# TG21_Slave_Device_Amply.net
KiCad netlist of a schematic drawn in Altium Designer
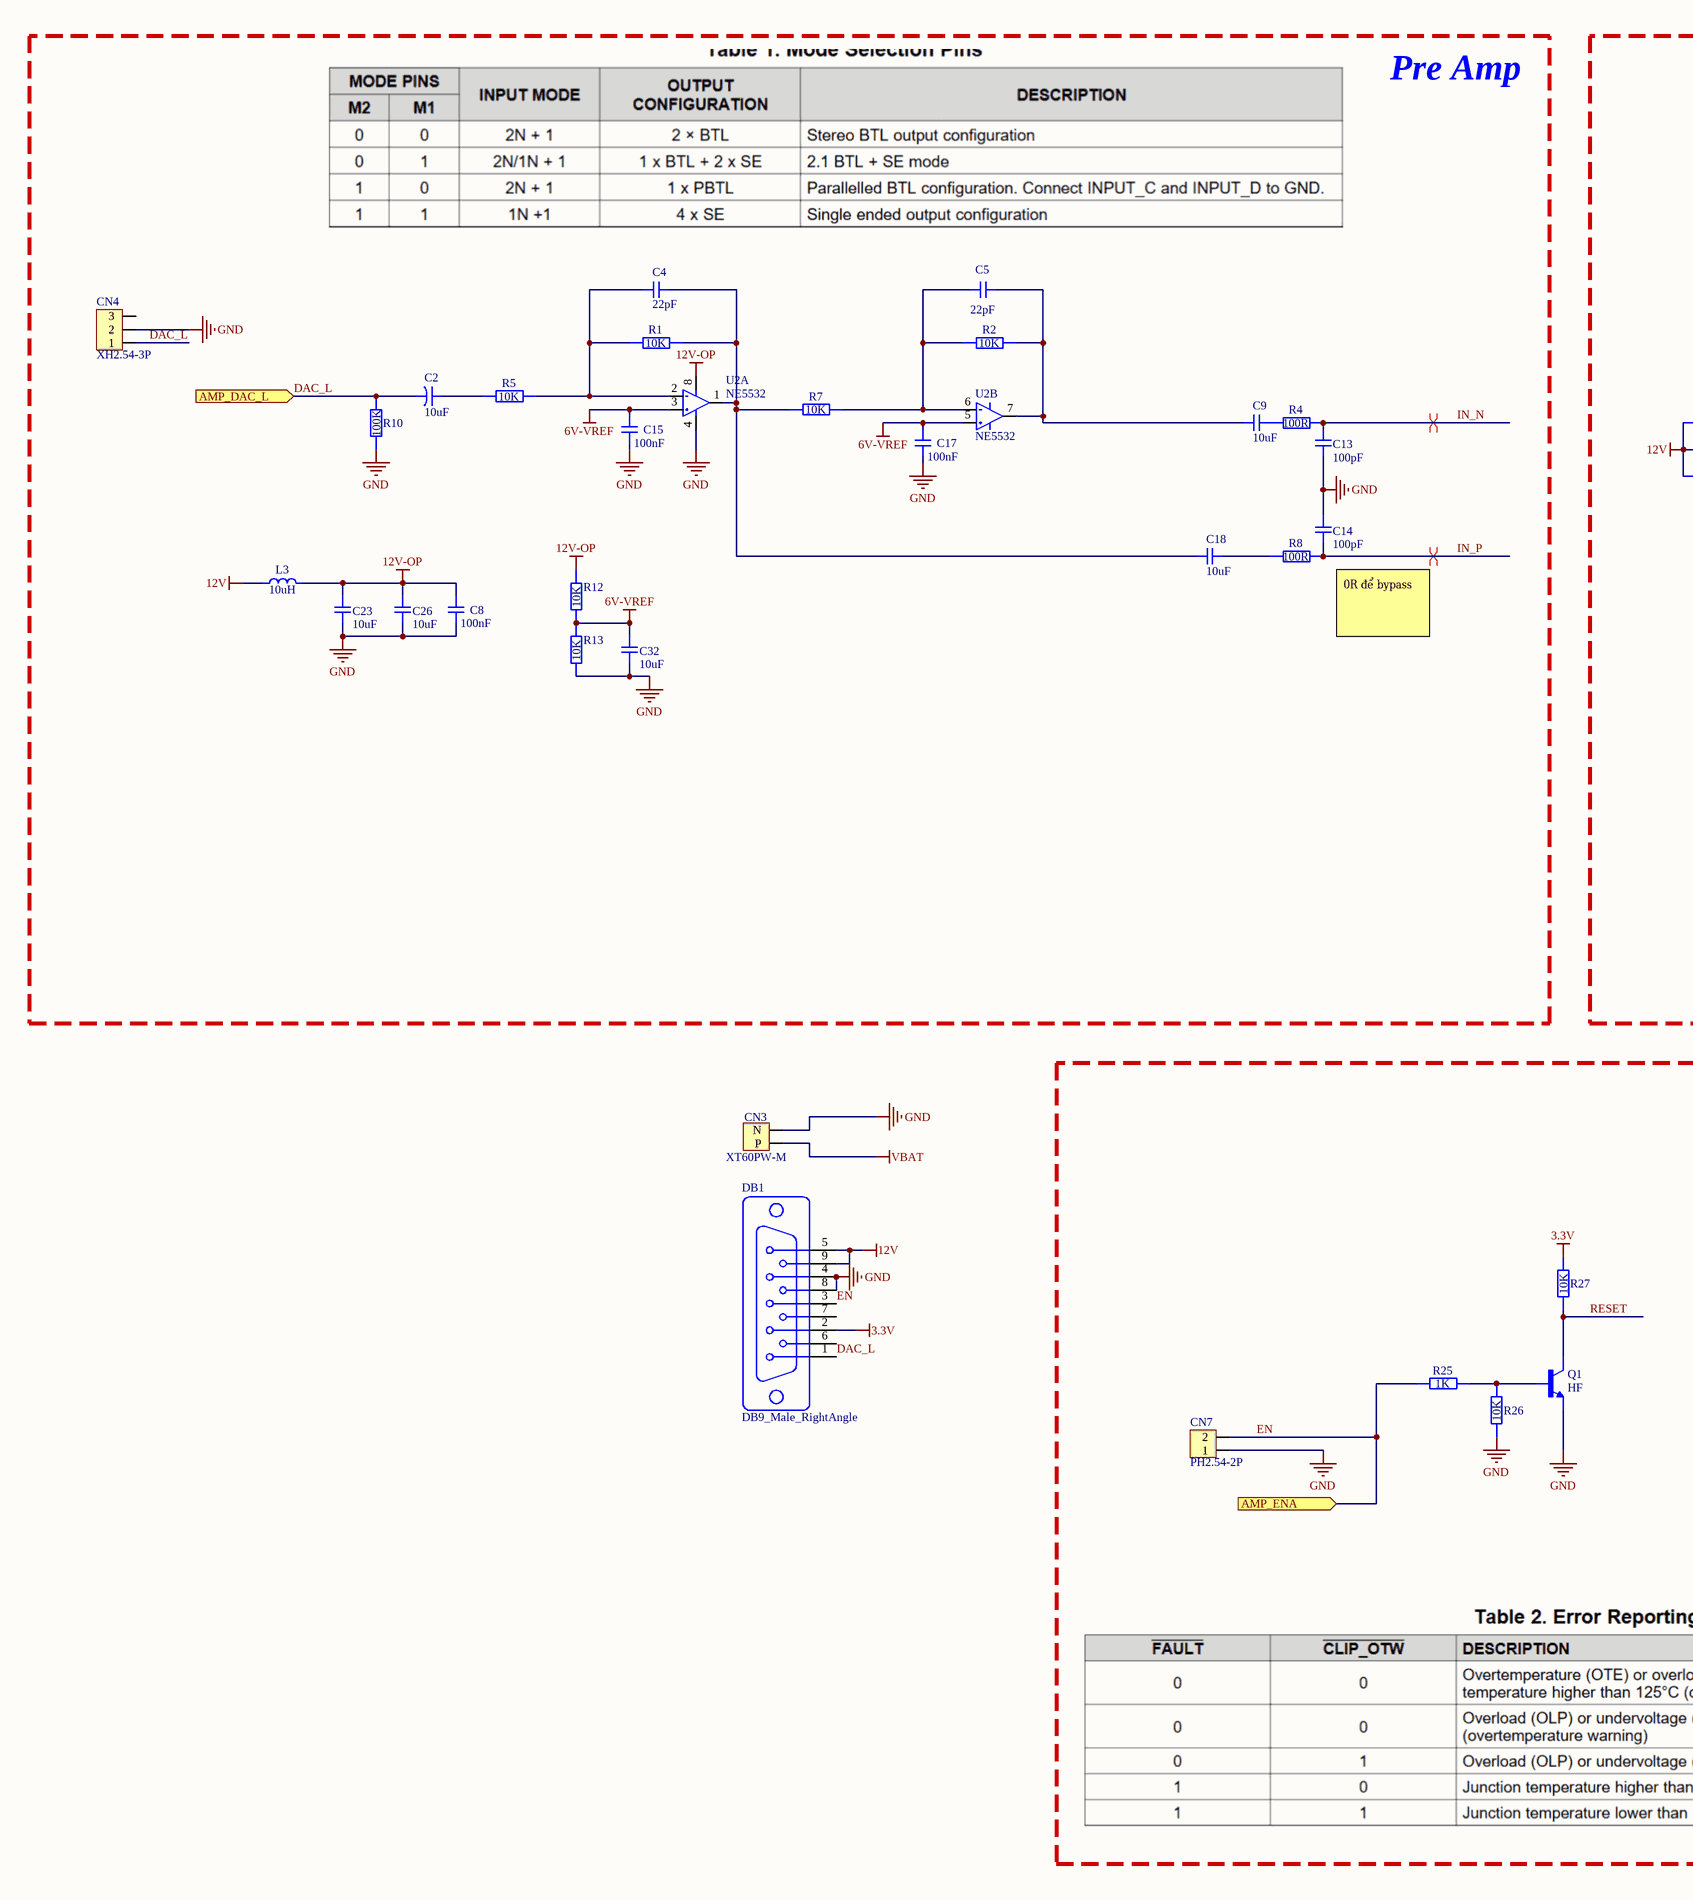
[diagram p0: TG21_Slave_Device_Amply.SchDoc, left]
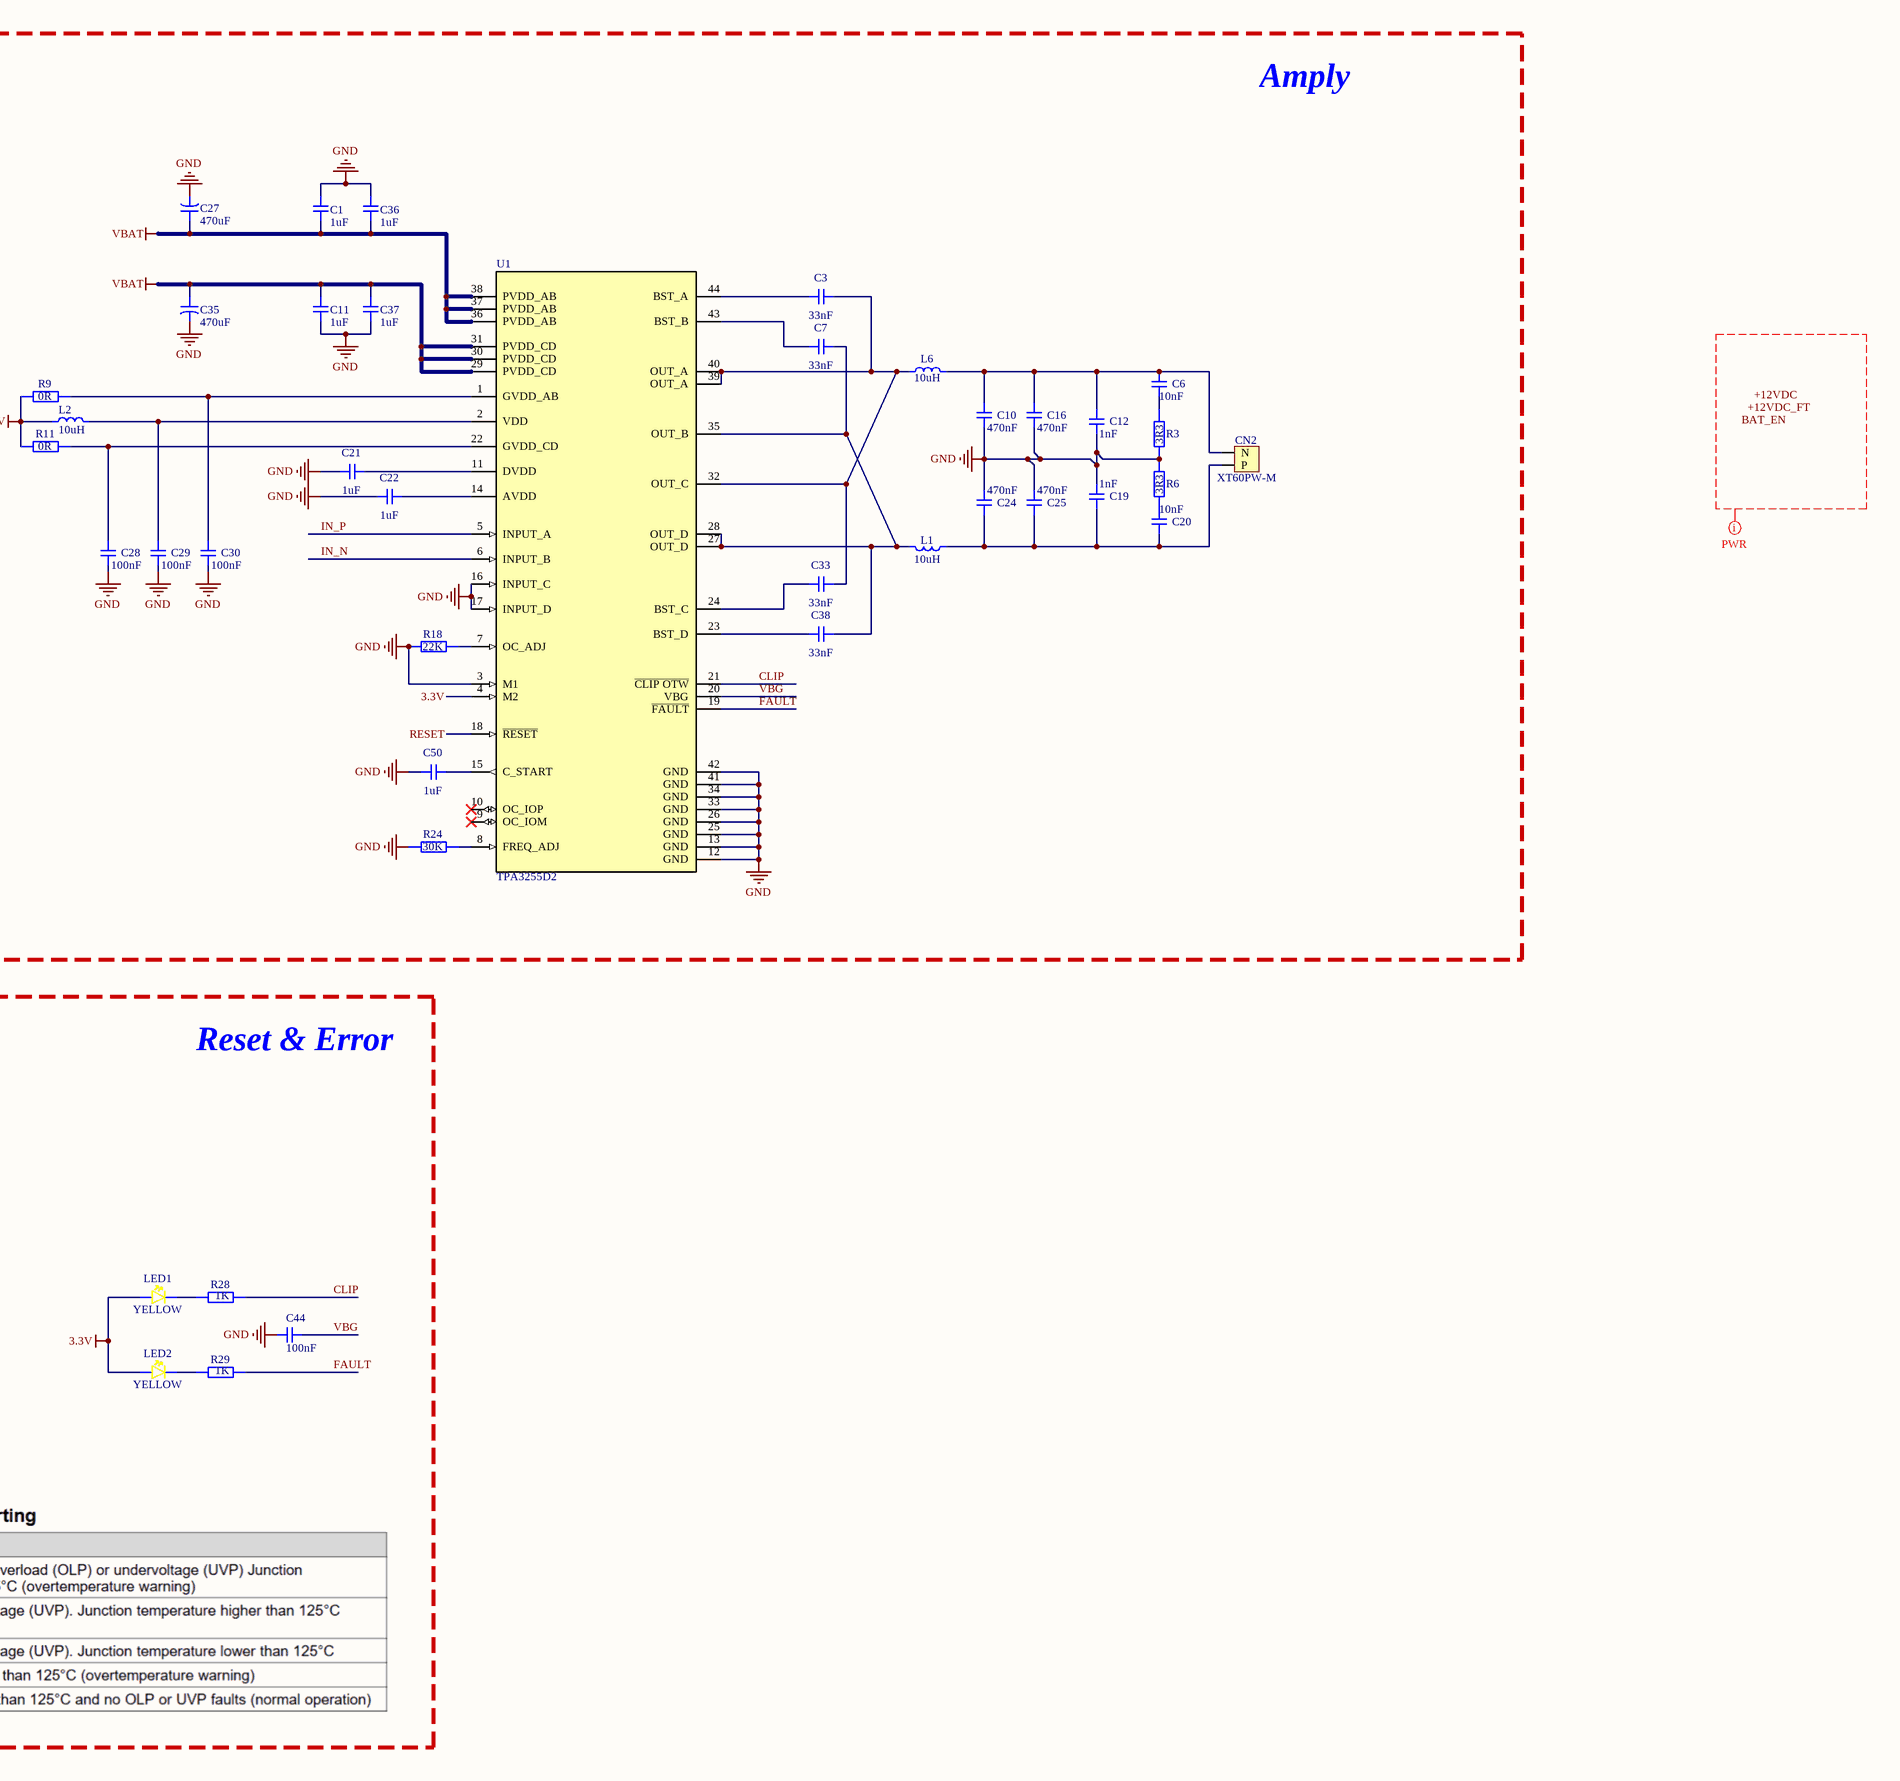
[diagram p1: TG21_Slave_Device_Amply.SchDoc, right]

(export (version "E")
  (design (tool "Eeschema 10.0.6"))
  (components
    (comp (ref "C1")
      (value "1uF")
      (footprint "CAP-0603")
      (description "1uF ±10% 50V Ceramic Capacitor X7R 0603")
      (fields (field (name "MANUFACTURER") "YAGEO") (field (name "MFR.PART #") "CC0603KRX7R9BB105"))
      (libsource (lib "CbyP") (part "CC0603KRX7R9BB105"))
    )
    (comp (ref "C2")
      (value "10uF")
      (footprint "PLUGIN,D5xL11mm")
      (description "10uF 50V Aluminum Electrolytic Capacitors Through Hole,D5xL11mm 5000hrs@105℃")
      (fields (field (name "MANUFACTURER") "Rubycon") (field (name "MFR.PART #") "50YXF10MEFC5X11"))
      (libsource (lib "CbyP") (part "50YXF10MEFC5X11"))
    )
    (comp (ref "C3")
      (value "33nF")
      (footprint "CAP-0603")
      (description "33nF ±10% 50V Ceramic Capacitor X7R 0603")
      (fields (field (name "MANUFACTURER") "YAGEO") (field (name "MFR.PART #") "CC0603KRX7R9BB333"))
      (libsource (lib "CbyP") (part "CC0603KRX7R9BB333"))
    )
    (comp (ref "C4")
      (value "22pF")
      (footprint "CAP-0603")
      (description "22pF ±5% 50V Ceramic Capacitor NP0 0603")
      (fields (field (name "MANUFACTURER") "YAGEO") (field (name "LCSC PART #") "C105620"))
      (libsource (lib "CbyP") (part "CC0603JRNPO9BN220"))
    )
    (comp (ref "C5")
      (value "22pF")
      (footprint "CAP-0603")
      (description "22pF ±5% 50V Ceramic Capacitor NP0 0603")
      (fields (field (name "MANUFACTURER") "YAGEO") (field (name "LCSC PART #") "C105620"))
      (libsource (lib "CbyP") (part "CC0603JRNPO9BN220"))
    )
    (comp (ref "C6")
      (value "10nF")
      (footprint "CAP-0603")
      (description "10nF ±5% 50V Ceramic Capacitor X7R 0603")
      (fields (field (name "MANUFACTURER") "YAGEO") (field (name "MFR.PART #") "CC0603JRX7R9BB103"))
      (libsource (lib "CbyP") (part "CC0603JRX7R9BB103"))
    )
    (comp (ref "C7")
      (value "33nF")
      (footprint "CAP-0603")
      (description "33nF ±10% 50V Ceramic Capacitor X7R 0603")
      (fields (field (name "MANUFACTURER") "YAGEO") (field (name "MFR.PART #") "CC0603KRX7R9BB333"))
      (libsource (lib "CbyP") (part "CC0603KRX7R9BB333"))
    )
    (comp (ref "C8")
      (value "100nF")
      (footprint "CAP-0603")
      (description "100nF ±10% 50V Ceramic Capacitor X7R 0603")
      (fields (field (name "MANUFACTURER") "YAGEO") (field (name "LCSC PART #") "C14663"))
      (libsource (lib "CbyP") (part "CC0603KRX7R9BB104"))
    )
    (comp (ref "C9")
      (value "10uF")
      (footprint "CAP-0603")
      (description "10uF ±20% 25V Ceramic Capacitor X5R 0603")
      (fields
        (field (name "MANUFACTURER") "Samsung Electro-Mechanics")
        (field (name "MFR.PART #") "CL10A106MA8NRNC")
      )
      (libsource (lib "CbyP") (part "CL10A106MA8NRNC"))
    )
    (comp (ref "C10")
      (value "470nF")
      (footprint "CAP-1206 - 1")
      (description "470nF ±10% 100V Ceramic Capacitor X7R 1206")
      (fields (field (name "MANUFACTURER") "FH") (field (name "MFR.PART #") "1206B474K101NT"))
      (libsource (lib "CbyP") (part "1206B474K101NT"))
    )
    (comp (ref "C11")
      (value "1uF")
      (footprint "CAP-0603")
      (description "1uF ±10% 50V Ceramic Capacitor X7R 0603")
      (fields (field (name "MANUFACTURER") "YAGEO") (field (name "MFR.PART #") "CC0603KRX7R9BB105"))
      (libsource (lib "CbyP") (part "CC0603KRX7R9BB105"))
    )
    (comp (ref "C12")
      (value "1nF")
      (footprint "CAP-0603")
      (description "1nF ±10% 50V Ceramic Capacitor X7R 0603")
      (fields (field (name "MANUFACTURER") "YAGEO") (field (name "LCSC PART #") "C100040"))
      (libsource (lib "CbyP") (part "CC0603KRX7R9BB102"))
    )
    (comp (ref "C13")
      (value "100pF")
      (footprint "CAP-0603")
      (description "100pF ±5% 50V Ceramic Capacitor C0G 0603")
      (fields
        (field (name "MANUFACTURER") "Samsung Electro-Mechanics")
        (field (name "MFR.PART #") "CL10C101JB8NNNC")
      )
      (libsource (lib "CbyP") (part "CL10C101JB8NNNC"))
    )
    (comp (ref "C14")
      (value "100pF")
      (footprint "CAP-0603")
      (description "100pF ±5% 50V Ceramic Capacitor C0G 0603")
      (fields
        (field (name "MANUFACTURER") "Samsung Electro-Mechanics")
        (field (name "MFR.PART #") "CL10C101JB8NNNC")
      )
      (libsource (lib "CbyP") (part "CL10C101JB8NNNC"))
    )
    (comp (ref "C15")
      (value "100nF")
      (footprint "CAP-0603")
      (description "100nF ±10% 50V Ceramic Capacitor X7R 0603")
      (fields (field (name "MANUFACTURER") "YAGEO") (field (name "LCSC PART #") "C14663"))
      (libsource (lib "CbyP") (part "CC0603KRX7R9BB104"))
    )
    (comp (ref "C16")
      (value "470nF")
      (footprint "CAP-1206 - 1")
      (description "470nF ±10% 100V Ceramic Capacitor X7R 1206")
      (fields (field (name "MANUFACTURER") "FH") (field (name "MFR.PART #") "1206B474K101NT"))
      (libsource (lib "CbyP") (part "1206B474K101NT"))
    )
    (comp (ref "C17")
      (value "100nF")
      (footprint "CAP-0603")
      (description "100nF ±10% 50V Ceramic Capacitor X7R 0603")
      (fields (field (name "MANUFACTURER") "YAGEO") (field (name "LCSC PART #") "C14663"))
      (libsource (lib "CbyP") (part "CC0603KRX7R9BB104"))
    )
    (comp (ref "C18")
      (value "10uF")
      (footprint "CAP-0603")
      (description "10uF ±20% 25V Ceramic Capacitor X5R 0603")
      (fields
        (field (name "MANUFACTURER") "Samsung Electro-Mechanics")
        (field (name "MFR.PART #") "CL10A106MA8NRNC")
      )
      (libsource (lib "CbyP") (part "CL10A106MA8NRNC"))
    )
    (comp (ref "C19")
      (value "1nF")
      (footprint "CAP-0603")
      (description "1nF ±10% 50V Ceramic Capacitor X7R 0603")
      (fields (field (name "MANUFACTURER") "YAGEO") (field (name "LCSC PART #") "C100040"))
      (libsource (lib "CbyP") (part "CC0603KRX7R9BB102"))
    )
    (comp (ref "C20")
      (value "10nF")
      (footprint "CAP-0603")
      (description "10nF ±5% 50V Ceramic Capacitor X7R 0603")
      (fields (field (name "MANUFACTURER") "YAGEO") (field (name "MFR.PART #") "CC0603JRX7R9BB103"))
      (libsource (lib "CbyP") (part "CC0603JRX7R9BB103"))
    )
    (comp (ref "C21")
      (value "1uF")
      (footprint "CAP-0603")
      (description "1uF ±10% 50V Ceramic Capacitor X7R 0603")
      (fields (field (name "MANUFACTURER") "YAGEO") (field (name "MFR.PART #") "CC0603KRX7R9BB105"))
      (libsource (lib "CbyP") (part "CC0603KRX7R9BB105"))
    )
    (comp (ref "C22")
      (value "1uF")
      (footprint "CAP-0603")
      (description "1uF ±10% 50V Ceramic Capacitor X7R 0603")
      (fields (field (name "MANUFACTURER") "YAGEO") (field (name "MFR.PART #") "CC0603KRX7R9BB105"))
      (libsource (lib "CbyP") (part "CC0603KRX7R9BB105"))
    )
    (comp (ref "C23")
      (value "10uF")
      (footprint "CAP-0603")
      (description "10uF ±20% 25V Ceramic Capacitor X5R 0603")
      (fields
        (field (name "MANUFACTURER") "Samsung Electro-Mechanics")
        (field (name "MFR.PART #") "CL10A106MA8NRNC")
      )
      (libsource (lib "CbyP") (part "CL10A106MA8NRNC"))
    )
    (comp (ref "C24")
      (value "470nF")
      (footprint "CAP-1206 - 1")
      (description "470nF ±10% 100V Ceramic Capacitor X7R 1206")
      (fields (field (name "MANUFACTURER") "FH") (field (name "MFR.PART #") "1206B474K101NT"))
      (libsource (lib "CbyP") (part "1206B474K101NT"))
    )
    (comp (ref "C25")
      (value "470nF")
      (footprint "CAP-1206 - 1")
      (description "470nF ±10% 100V Ceramic Capacitor X7R 1206")
      (fields (field (name "MANUFACTURER") "FH") (field (name "MFR.PART #") "1206B474K101NT"))
      (libsource (lib "CbyP") (part "1206B474K101NT"))
    )
    (comp (ref "C26")
      (value "10uF")
      (footprint "CAP-0603")
      (description "10uF ±20% 25V Ceramic Capacitor X5R 0603")
      (fields
        (field (name "MANUFACTURER") "Samsung Electro-Mechanics")
        (field (name "MFR.PART #") "CL10A106MA8NRNC")
      )
      (libsource (lib "CbyP") (part "CL10A106MA8NRNC"))
    )
    (comp (ref "C27")
      (value "470uF")
      (footprint "Plugin,D10xL20mm")
      (description "470uF 50V Aluminum Electrolytic Capacitors Through Hole,D10xL20mm 2000hrs@105℃")
      (fields (field (name "MANUFACTURER") "Rubycon") (field (name "MFR.PART #") "50PX470MEFC10X20"))
      (libsource (lib "CbyP") (part "50PX470MEFC10X20"))
    )
    (comp (ref "C28")
      (value "100nF")
      (footprint "CAP-0603")
      (description "100nF ±10% 50V Ceramic Capacitor X7R 0603")
      (fields (field (name "MANUFACTURER") "YAGEO") (field (name "LCSC PART #") "C14663"))
      (libsource (lib "CbyP") (part "CC0603KRX7R9BB104"))
    )
    (comp (ref "C29")
      (value "100nF")
      (footprint "CAP-0603")
      (description "100nF ±10% 50V Ceramic Capacitor X7R 0603")
      (fields (field (name "MANUFACTURER") "YAGEO") (field (name "LCSC PART #") "C14663"))
      (libsource (lib "CbyP") (part "CC0603KRX7R9BB104"))
    )
    (comp (ref "C30")
      (value "100nF")
      (footprint "CAP-0603")
      (description "100nF ±10% 50V Ceramic Capacitor X7R 0603")
      (fields (field (name "MANUFACTURER") "YAGEO") (field (name "LCSC PART #") "C14663"))
      (libsource (lib "CbyP") (part "CC0603KRX7R9BB104"))
    )
    (comp (ref "C32")
      (value "10uF")
      (footprint "CAP-0603")
      (description "10uF ±20% 25V Ceramic Capacitor X5R 0603")
      (fields
        (field (name "MANUFACTURER") "Samsung Electro-Mechanics")
        (field (name "MFR.PART #") "CL10A106MA8NRNC")
      )
      (libsource (lib "CbyP") (part "CL10A106MA8NRNC"))
    )
    (comp (ref "C33")
      (value "33nF")
      (footprint "CAP-0603")
      (description "33nF ±10% 50V Ceramic Capacitor X7R 0603")
      (fields (field (name "MANUFACTURER") "YAGEO") (field (name "MFR.PART #") "CC0603KRX7R9BB333"))
      (libsource (lib "CbyP") (part "CC0603KRX7R9BB333"))
    )
    (comp (ref "C35")
      (value "470uF")
      (footprint "Plugin,D10xL20mm")
      (description "470uF 50V Aluminum Electrolytic Capacitors Through Hole,D10xL20mm 2000hrs@105℃")
      (fields (field (name "MANUFACTURER") "Rubycon") (field (name "MFR.PART #") "50PX470MEFC10X20"))
      (libsource (lib "CbyP") (part "50PX470MEFC10X20"))
    )
    (comp (ref "C36")
      (value "1uF")
      (footprint "CAP-0603")
      (description "1uF ±10% 50V Ceramic Capacitor X7R 0603")
      (fields (field (name "MANUFACTURER") "YAGEO") (field (name "MFR.PART #") "CC0603KRX7R9BB105"))
      (libsource (lib "CbyP") (part "CC0603KRX7R9BB105"))
    )
    (comp (ref "C37")
      (value "1uF")
      (footprint "CAP-0603")
      (description "1uF ±10% 50V Ceramic Capacitor X7R 0603")
      (fields (field (name "MANUFACTURER") "YAGEO") (field (name "MFR.PART #") "CC0603KRX7R9BB105"))
      (libsource (lib "CbyP") (part "CC0603KRX7R9BB105"))
    )
    (comp (ref "C38")
      (value "33nF")
      (footprint "CAP-0603")
      (description "33nF ±10% 50V Ceramic Capacitor X7R 0603")
      (fields (field (name "MANUFACTURER") "YAGEO") (field (name "MFR.PART #") "CC0603KRX7R9BB333"))
      (libsource (lib "CbyP") (part "CC0603KRX7R9BB333"))
    )
    (comp (ref "C44")
      (value "100nF")
      (footprint "CAP-0603")
      (description "100nF ±10% 50V Ceramic Capacitor X7R 0603")
      (fields (field (name "MANUFACTURER") "YAGEO") (field (name "LCSC PART #") "C14663"))
      (libsource (lib "CbyP") (part "CC0603KRX7R9BB104"))
    )
    (comp (ref "C50")
      (value "1uF")
      (footprint "CAP-0603")
      (description "1uF ±10% 50V Ceramic Capacitor X7R 0603")
      (fields (field (name "MANUFACTURER") "YAGEO") (field (name "MFR.PART #") "CC0603KRX7R9BB105"))
      (libsource (lib "CbyP") (part "CC0603KRX7R9BB105"))
    )
    (comp (ref "CN2")
      (value "XT60PW-M")
      (footprint "XT60PW-M")
      (description "Banana and Tip Connector Adapters RoHS")
      (fields (field (name "MANUFACTURER") "Changzhou Amass Elec") (field (name "LCSC PART #") "C98732"))
      (libsource (lib "") (part "XT60PW-M_1"))
    )
    (comp (ref "CN3")
      (value "XT60PW-M")
      (footprint "XT60PW-M")
      (description "Banana and Tip Connector Adapters RoHS")
      (fields (field (name "MANUFACTURER") "Changzhou Amass Elec") (field (name "LCSC PART #") "C98732"))
      (libsource (lib "CbyP") (part "XT60PW-M"))
    )
    (comp (ref "CN4")
      (value "XH2.54-3P")
      (footprint "Plugin,P=2.54mm,3P")
      (description "Connector Header 3 position 2.5mm Pitch 3A Through Hole -25℃~+85℃")
      (fields (field (name "MANUFACTURER") "Bossie") (field (name "MFR.PART #") "BX-XH2.54-3PZZ"))
      (libsource (lib "CbyP") (part "BX-XH2.54-3PZZ"))
    )
    (comp (ref "CN7")
      (value "PH2.54-2P")
      (footprint "Plugin,P=2.54mm,2P,Pin Headers")
      (description "Pin Header 2 Position 2.54mm Pitch Single Row Through Hole -40℃~+105℃")
      (fields (field (name "MANUFACTURER") "JXTCONN") (field (name "MFR.PART #") "PH2.54-1X2P-H25"))
      (libsource (lib "CbyP") (part "PH2.54-1X2P-H25"))
    )
    (comp (ref "DB1")
      (value "DB9_Male_RightAngle")
      (footprint "D-Sub, 9P, Through Hole,Right Angle")
      (description "Connector D-Sub, Male 9 Position 2 Row Through Hole, Right Angle")
      (fields (field (name "MANUFACTURER") "XUNPU") (field (name "MFR. PART #") "D-SUB-DR-9PCG-BB"))
      (libsource (lib "TG21_Slave_Device_Amply_V1.2") (part "DB9_Male_RightAngle"))
    )
    (comp (ref "L1")
      (value "10uH")
      (footprint "RM6")
      (description "10uH SMD, 21.5x22.5mm, 5mΩ, Isat 12A")
      (fields (field (name "MANUFACTURER") "NO") (field (name "MFR.PART #") "MTP2012S-100MC"))
      (libsource (lib "CbyP") (part "RM6-10UH18A"))
    )
    (comp (ref "L2")
      (value "10uH")
      (footprint "CAP-0603")
      (description "250mA 10uH 90mA 1.05Ω Multilayer inductor ±20% 0603 Fixed Inductors RoHS")
      (fields (field (name "MANUFACTURER") "TDK") (field (name "MFR.PART #") "MLZ1608M100WT000"))
      (libsource (lib "CbyP") (part "MLZ1608M100WT000"))
    )
    (comp (ref "L3")
      (value "10uH")
      (footprint "SMD,4x4x1.8mm(4018)")
      (description "1.2A 10uH Magnetic Shielded Inductor ±20% 1.6A 234mΩ SMD,4x4mm Fixed Inductors RoHS")
      (fields (field (name "MANUFACTURER") "cjiang") (field (name "MFR.PART #") "FNR4018S100MT"))
      (libsource (lib "CbyP") (part "FNR4018S100MT"))
    )
    (comp (ref "L6")
      (value "10uH")
      (footprint "RM6")
      (description "10uH SMD, 21.5x22.5mm, 5mΩ, Isat 12A")
      (fields (field (name "MANUFACTURER") "NO") (field (name "MFR.PART #") "MTP2012S-100MC"))
      (libsource (lib "CbyP") (part "RM6-10UH18A"))
    )
    (comp (ref "LED1")
      (value "YELLOW")
      (footprint "LED-0603")
      (description "0603 YELLOW")
      (fields (field (name "MANUFACTURER") "NO") (field (name "MFR.PART #") "KO-0603QYGC/6"))
      (libsource (lib "CbyP") (part "KO-0603QYGC/6"))
    )
    (comp (ref "LED2")
      (value "YELLOW")
      (footprint "LED-0603")
      (description "0603 YELLOW")
      (fields (field (name "MANUFACTURER") "NO") (field (name "MFR.PART #") "KO-0603QYGC/6"))
      (libsource (lib "CbyP") (part "KO-0603QYGC/6"))
    )
    (comp (ref "Q1")
      (value "HF")
      (footprint "SOT-23")
      (description "Bipolar (BJT) Transistor NPN 50V 0.15A 80MHz 200mW Surface Mount SOT-23")
      (fields (field (name "MANUFACTURER") "R+O") (field (name "MFR.PART #") "2SC1815"))
      (libsource (lib "CbyP") (part "2SC1815"))
    )
    (comp (ref "R1")
      (value "10K")
      (footprint "RES-0603")
      (description "100mW 10kΩ 75V Thick Film Resistor ±100ppm/℃ ±1% 0603 Chip Resistor - Surface Mount RoHS")
      (fields (field (name "MANUFACTURER") "YAGEO") (field (name "LCSC PART #") "C98220"))
      (libsource (lib "CbyP") (part "RC0603FR-0710KL"))
    )
    (comp (ref "R2")
      (value "10K")
      (footprint "RES-0603")
      (description "100mW 10kΩ 75V Thick Film Resistor ±100ppm/℃ ±1% 0603 Chip Resistor - Surface Mount RoHS")
      (fields (field (name "MANUFACTURER") "YAGEO") (field (name "LCSC PART #") "C98220"))
      (libsource (lib "CbyP") (part "RC0603FR-0710KL"))
    )
    (comp (ref "R3")
      (value "3R3")
      (footprint "RES-0603")
      (description "100mW 3.3Ω 75V Thick Film Resistor ±1% ±200ppm/℃ 0603 Chip Resistor - Surface Mount RoHS")
      (fields (field (name "MANUFACTURER") "YAGEO") (field (name "MFR.PART #") "RC0603FR-073R3L"))
      (libsource (lib "CbyP") (part "RC0603FR-073R3L"))
    )
    (comp (ref "R4")
      (value "100R")
      (footprint "RES-0603")
      (description "100mW 100Ω 75V Thick Film Resistor ±100ppm/℃ ±1% 0603 Chip Resistor - Surface Mount RoHS")
      (fields (field (name "MANUFACTURER") "YAGEO") (field (name "MFR.PART #") "RC0603FR-07100KL"))
      (libsource (lib "CbyP") (part "RC0603FR-07100RL"))
    )
    (comp (ref "R5")
      (value "10K")
      (footprint "RES-0603")
      (description "100mW 10kΩ 75V Thick Film Resistor ±100ppm/℃ ±1% 0603 Chip Resistor - Surface Mount RoHS")
      (fields (field (name "MANUFACTURER") "YAGEO") (field (name "LCSC PART #") "C98220"))
      (libsource (lib "CbyP") (part "RC0603FR-0710KL"))
    )
    (comp (ref "R6")
      (value "3R3")
      (footprint "RES-0603")
      (description "100mW 3.3Ω 75V Thick Film Resistor ±1% ±200ppm/℃ 0603 Chip Resistor - Surface Mount RoHS")
      (fields (field (name "MANUFACTURER") "YAGEO") (field (name "MFR.PART #") "RC0603FR-073R3L"))
      (libsource (lib "CbyP") (part "RC0603FR-073R3L"))
    )
    (comp (ref "R7")
      (value "10K")
      (footprint "RES-0603")
      (description "100mW 10kΩ 75V Thick Film Resistor ±100ppm/℃ ±1% 0603 Chip Resistor - Surface Mount RoHS")
      (fields (field (name "MANUFACTURER") "YAGEO") (field (name "LCSC PART #") "C98220"))
      (libsource (lib "CbyP") (part "RC0603FR-0710KL"))
    )
    (comp (ref "R8")
      (value "100R")
      (footprint "RES-0603")
      (description "100mW 100Ω 75V Thick Film Resistor ±100ppm/℃ ±1% 0603 Chip Resistor - Surface Mount RoHS")
      (fields (field (name "MANUFACTURER") "YAGEO") (field (name "MFR.PART #") "RC0603FR-07100KL"))
      (libsource (lib "CbyP") (part "RC0603FR-07100RL"))
    )
    (comp (ref "R9")
      (value "0R")
      (footprint "RES-0603")
      (description "0Ω 100mW 75V Thick Film Resistor ±1% 0603 Chip Resistor - Surface Mount RoHS")
      (fields (field (name "MFR.PART #") "RC0603FR-070RL") (field (name "MANUFACTURER") "YAGEO"))
      (libsource (lib "CbyP") (part "RC0603FR-070RL"))
    )
    (comp (ref "R10")
      (value "100K")
      (footprint "RES-0603")
      (description "100mW 100kΩ 75V Thick Film Resistor ±100ppm/℃ ±1% 0603 Chip Resistor - Surface Mount RoHS")
      (fields (field (name "MANUFACTURER") "YAGEO") (field (name "MFR.PART #") "RC0603FR-07100KL"))
      (libsource (lib "CbyP") (part "RC0603FR-07100KL"))
    )
    (comp (ref "R11")
      (value "0R")
      (footprint "RES-0603")
      (description "0Ω 100mW 75V Thick Film Resistor ±1% 0603 Chip Resistor - Surface Mount RoHS")
      (fields (field (name "MFR.PART #") "RC0603FR-070RL") (field (name "MANUFACTURER") "YAGEO"))
      (libsource (lib "CbyP") (part "RC0603FR-070RL"))
    )
    (comp (ref "R12")
      (value "10K")
      (footprint "RES-0603")
      (description "100mW 10kΩ 75V Thick Film Resistor ±100ppm/℃ ±1% 0603 Chip Resistor - Surface Mount RoHS")
      (fields (field (name "MANUFACTURER") "YAGEO") (field (name "LCSC PART #") "C98220"))
      (libsource (lib "CbyP") (part "RC0603FR-0710KL"))
    )
    (comp (ref "R13")
      (value "10K")
      (footprint "RES-0603")
      (description "100mW 10kΩ 75V Thick Film Resistor ±100ppm/℃ ±1% 0603 Chip Resistor - Surface Mount RoHS")
      (fields (field (name "MANUFACTURER") "YAGEO") (field (name "LCSC PART #") "C98220"))
      (libsource (lib "CbyP") (part "RC0603FR-0710KL"))
    )
    (comp (ref "R18")
      (value "22K")
      (footprint "RES-0603")
      (description "100mW 22kΩ 75V Thick Film Resistor ±100ppm/℃ ±1% 0603 Chip Resistor - Surface Mount RoHS")
      (fields (field (name "MANUFACTURER") "YAGEO") (field (name "MFR.PART #") "RC0603FR-0722KL"))
      (libsource (lib "CbyP") (part "RC0603FR-0722KL"))
    )
    (comp (ref "R24")
      (value "30K")
      (footprint "RES-0603")
      (description "100mW 30kΩ 75V Thick Film Resistor ±100ppm/℃ ±1% 0603 Chip Resistor - Surface Mount RoHS")
      (fields (field (name "MANUFACTURER") "YAGEO") (field (name "MFR.PART #") "RC0603FR-0730KL"))
      (libsource (lib "CbyP") (part "RC0603FR-0730KL"))
    )
    (comp (ref "R25")
      (value "1K")
      (footprint "RES-0603")
      (description "100mW 1kΩ 75V Thick Film Resistor ±100ppm/℃ ±1% 0603 Chip Resistor - Surface Mount RoHS")
      (fields (field (name "MANUFACTURER") "YAGEO") (field (name "MFR.PART #") "RC0603FR-071KL"))
      (libsource (lib "CbyP") (part "RC0603FR-071KL"))
    )
    (comp (ref "R26")
      (value "10K")
      (footprint "RES-0603")
      (description "100mW 10kΩ 75V Thick Film Resistor ±100ppm/℃ ±1% 0603 Chip Resistor - Surface Mount RoHS")
      (fields (field (name "MANUFACTURER") "YAGEO") (field (name "LCSC PART #") "C98220"))
      (libsource (lib "CbyP") (part "RC0603FR-0710KL"))
    )
    (comp (ref "R27")
      (value "10K")
      (footprint "RES-0603")
      (description "100mW 10kΩ 75V Thick Film Resistor ±100ppm/℃ ±1% 0603 Chip Resistor - Surface Mount RoHS")
      (fields (field (name "MANUFACTURER") "YAGEO") (field (name "LCSC PART #") "C98220"))
      (libsource (lib "CbyP") (part "RC0603FR-0710KL"))
    )
    (comp (ref "R28")
      (value "1K")
      (footprint "RES-0603")
      (description "100mW 1kΩ 75V Thick Film Resistor ±100ppm/℃ ±1% 0603 Chip Resistor - Surface Mount RoHS")
      (fields (field (name "MANUFACTURER") "YAGEO") (field (name "MFR.PART #") "RC0603FR-071KL"))
      (libsource (lib "CbyP") (part "RC0603FR-071KL"))
    )
    (comp (ref "R29")
      (value "1K")
      (footprint "RES-0603")
      (description "100mW 1kΩ 75V Thick Film Resistor ±100ppm/℃ ±1% 0603 Chip Resistor - Surface Mount RoHS")
      (fields (field (name "MANUFACTURER") "YAGEO") (field (name "MFR.PART #") "RC0603FR-071KL"))
      (libsource (lib "CbyP") (part "RC0603FR-071KL"))
    )
    (comp (ref "U1")
      (value "TPA3255D2")
      (footprint "HTSSOP-44-6.1mm-TPA3255")
      (description "Amplifier IC 2-Channel (Stereo) Class D 44-HTSSOP")
      (fields (field (name "MANUFACTURER") "Texas Instruments"))
      (libsource (lib "TG21_Slave_Device_Amply_V1.2") (part "TPA3255"))
    )
    (comp (ref "U2")
      (value "NE5532")
      (footprint "SOIC-8")
      (description "2 500uV 9V/us 100dB 1uA 16mA 10MHz SOIC-8 Instrumentation, Op Amps, Buffer Amps RoHS")
      (fields (field (name "MANUFACTURER") "TI") (field (name "MFR. PART #") "NE5532DR"))
      (libsource (lib "TG21_Slave_Device_Amply_V1.2") (part "NE5532"))
    )
  )
  (nets
    (net (code "4") (name "/CLIP") (class "Default")
      (node (ref "R28") (pin "2") (pinfunction "2_2") (pintype "passive"))
      (node (ref "U1") (pin "21") (pinfunction "CLIP_OTW_21") (pintype "open_collector"))
    )
    (net (code "5") (name "/DAC_L") (class "Default")
      (node (ref "C2") (pin "2") (pinfunction "2_2") (pintype "passive"))
      (node (ref "CN4") (pin "1") (pinfunction "1_1") (pintype "passive"))
      (node (ref "DB1") (pin "1") (pinfunction "1_1") (pintype "passive"))
      (node (ref "R10") (pin "1") (pinfunction "1_1") (pintype "passive"))
    )
    (net (code "6") (name "/EN") (class "Default")
      (node (ref "CN7") (pin "2") (pinfunction "2_2") (pintype "passive"))
      (node (ref "DB1") (pin "3") (pinfunction "3_3") (pintype "passive"))
      (node (ref "R25") (pin "1") (pinfunction "1_1") (pintype "passive"))
    )
    (net (code "7") (name "/FAULT") (class "Default")
      (node (ref "R29") (pin "2") (pinfunction "2_2") (pintype "passive"))
      (node (ref "U1") (pin "19") (pinfunction "~{FAULT}_19") (pintype "open_collector"))
    )
    (net (code "8") (name "/IN_N") (class "Default")
      (node (ref "C13") (pin "1") (pinfunction "1_1") (pintype "passive"))
      (node (ref "R4") (pin "2") (pinfunction "2_2") (pintype "passive"))
      (node (ref "U1") (pin "6") (pinfunction "INPUT_B_6") (pintype "input"))
    )
    (net (code "9") (name "/IN_P") (class "Default")
      (node (ref "C14") (pin "2") (pinfunction "2_2") (pintype "passive"))
      (node (ref "R8") (pin "2") (pinfunction "2_2") (pintype "passive"))
      (node (ref "U1") (pin "5") (pinfunction "INPUT_A_5") (pintype "input"))
    )
    (net (code "10") (name "/RESET") (class "Default")
      (node (ref "Q1") (pin "3") (pinfunction "C_3") (pintype "passive"))
      (node (ref "R27") (pin "1") (pinfunction "1_1") (pintype "passive"))
      (node (ref "U1") (pin "18") (pinfunction "~{RESET}_18") (pintype "input"))
    )
    (net (code "11") (name "/VBG") (class "Default")
      (node (ref "C44") (pin "2") (pinfunction "2_2") (pintype "passive"))
      (node (ref "U1") (pin "20") (pinfunction "VBG_20") (pintype "passive"))
    )
    (net (code "12") (name "3.3V") (class "Default")
      (node (ref "DB1") (pin "2") (pinfunction "2_2") (pintype "passive"))
      (node (ref "LED1") (pin "1") (pinfunction "A_1") (pintype "passive"))
      (node (ref "LED2") (pin "1") (pinfunction "A_1") (pintype "passive"))
      (node (ref "R27") (pin "2") (pinfunction "2_2") (pintype "passive"))
      (node (ref "U1") (pin "4") (pinfunction "M2_4") (pintype "input"))
    )
    (net (code "13") (name "6V-VREF") (class "Default")
      (node (ref "C15") (pin "1") (pinfunction "1_1") (pintype "passive"))
      (node (ref "C17") (pin "1") (pinfunction "1_1") (pintype "passive"))
      (node (ref "C32") (pin "1") (pinfunction "1_1") (pintype "passive"))
      (node (ref "R12") (pin "1") (pinfunction "1_1") (pintype "passive"))
      (node (ref "R13") (pin "2") (pinfunction "2_2") (pintype "passive"))
      (node (ref "U2") (pin "3") (pinfunction "IN1+_3") (pintype "passive"))
      (node (ref "U2") (pin "5") (pinfunction "IN2+_5") (pintype "passive"))
    )
    (net (code "14") (name "12V") (class "Default")
      (node (ref "DB1") (pin "5") (pinfunction "5_5") (pintype "passive"))
      (node (ref "DB1") (pin "9") (pinfunction "9_9") (pintype "passive"))
      (node (ref "L2") (pin "1") (pinfunction "1_1") (pintype "passive"))
      (node (ref "L3") (pin "1") (pinfunction "1_1") (pintype "passive"))
      (node (ref "R11") (pin "1") (pinfunction "1_1") (pintype "passive"))
      (node (ref "R9") (pin "1") (pinfunction "1_1") (pintype "passive"))
    )
    (net (code "15") (name "12V-OP") (class "Default")
      (node (ref "C23") (pin "1") (pinfunction "1_1") (pintype "passive"))
      (node (ref "C26") (pin "1") (pinfunction "1_1") (pintype "passive"))
      (node (ref "C8") (pin "1") (pinfunction "1_1") (pintype "passive"))
      (node (ref "L3") (pin "2") (pinfunction "2_2") (pintype "passive"))
      (node (ref "R12") (pin "2") (pinfunction "2_2") (pintype "passive"))
      (node (ref "U2") (pin "8") (pinfunction "VCC_8") (pintype "passive"))
    )
    (net (code "16") (name "GND") (class "Default")
      (node (ref "C1") (pin "1") (pinfunction "1_1") (pintype "passive"))
      (node (ref "C10") (pin "2") (pinfunction "2_2") (pintype "passive"))
      (node (ref "C11") (pin "2") (pinfunction "2_2") (pintype "passive"))
      (node (ref "C12") (pin "2") (pinfunction "2_2") (pintype "passive"))
      (node (ref "C13") (pin "2") (pinfunction "2_2") (pintype "passive"))
      (node (ref "C14") (pin "1") (pinfunction "1_1") (pintype "passive"))
      (node (ref "C15") (pin "2") (pinfunction "2_2") (pintype "passive"))
      (node (ref "C16") (pin "2") (pinfunction "2_2") (pintype "passive"))
      (node (ref "C17") (pin "2") (pinfunction "2_2") (pintype "passive"))
      (node (ref "C19") (pin "1") (pinfunction "1_1") (pintype "passive"))
      (node (ref "C21") (pin "2") (pinfunction "2_2") (pintype "passive"))
      (node (ref "C22") (pin "2") (pinfunction "2_2") (pintype "passive"))
      (node (ref "C23") (pin "2") (pinfunction "2_2") (pintype "passive"))
      (node (ref "C24") (pin "1") (pinfunction "1_1") (pintype "passive"))
      (node (ref "C25") (pin "1") (pinfunction "1_1") (pintype "passive"))
      (node (ref "C26") (pin "2") (pinfunction "2_2") (pintype "passive"))
      (node (ref "C27") (pin "2") (pinfunction "2_2") (pintype "passive"))
      (node (ref "C28") (pin "2") (pinfunction "2_2") (pintype "passive"))
      (node (ref "C29") (pin "2") (pinfunction "2_2") (pintype "passive"))
      (node (ref "C30") (pin "2") (pinfunction "2_2") (pintype "passive"))
      (node (ref "C32") (pin "2") (pinfunction "2_2") (pintype "passive"))
      (node (ref "C35") (pin "2") (pinfunction "2_2") (pintype "passive"))
      (node (ref "C36") (pin "1") (pinfunction "1_1") (pintype "passive"))
      (node (ref "C37") (pin "2") (pinfunction "2_2") (pintype "passive"))
      (node (ref "C44") (pin "1") (pinfunction "1_1") (pintype "passive"))
      (node (ref "C50") (pin "2") (pinfunction "2_2") (pintype "passive"))
      (node (ref "C8") (pin "2") (pinfunction "2_2") (pintype "passive"))
      (node (ref "CN3") (pin "2") (pinfunction "N_2") (pintype "passive"))
      (node (ref "CN4") (pin "2") (pinfunction "2_2") (pintype "passive"))
      (node (ref "CN7") (pin "1") (pinfunction "1_1") (pintype "passive"))
      (node (ref "DB1") (pin "4") (pinfunction "4_4") (pintype "passive"))
      (node (ref "DB1") (pin "8") (pinfunction "8_8") (pintype "passive"))
      (node (ref "Q1") (pin "2") (pinfunction "E_2") (pintype "passive"))
      (node (ref "R10") (pin "2") (pinfunction "2_2") (pintype "passive"))
      (node (ref "R13") (pin "1") (pinfunction "1_1") (pintype "passive"))
      (node (ref "R18") (pin "1") (pinfunction "1_1") (pintype "passive"))
      (node (ref "R24") (pin "1") (pinfunction "1_1") (pintype "passive"))
      (node (ref "R26") (pin "1") (pinfunction "1_1") (pintype "passive"))
      (node (ref "R3") (pin "1") (pinfunction "1_1") (pintype "passive"))
      (node (ref "R6") (pin "2") (pinfunction "2_2") (pintype "passive"))
      (node (ref "U1") (pin "12") (pinfunction "GND_12") (pintype "power_in"))
      (node (ref "U1") (pin "13") (pinfunction "GND_13") (pintype "power_in"))
      (node (ref "U1") (pin "16") (pinfunction "INPUT_C_16") (pintype "input"))
      (node (ref "U1") (pin "17") (pinfunction "INPUT_D_17") (pintype "input"))
      (node (ref "U1") (pin "25") (pinfunction "GND_25") (pintype "power_in"))
      (node (ref "U1") (pin "26") (pinfunction "GND_26") (pintype "power_in"))
      (node (ref "U1") (pin "3") (pinfunction "M1_3") (pintype "input"))
      (node (ref "U1") (pin "33") (pinfunction "GND_33") (pintype "power_in"))
      (node (ref "U1") (pin "34") (pinfunction "GND_34") (pintype "power_in"))
      (node (ref "U1") (pin "41") (pinfunction "GND_41") (pintype "power_in"))
      (node (ref "U1") (pin "42") (pinfunction "GND_42") (pintype "power_in"))
      (node (ref "U2") (pin "4") (pinfunction "GND_4") (pintype "passive"))
    )
    (net (code "17") (name "Net-(C2-Pad1)") (class "Default")
      (node (ref "C2") (pin "1") (pinfunction "1_1") (pintype "passive"))
      (node (ref "R5") (pin "1") (pinfunction "1_1") (pintype "passive"))
    )
    (net (code "18") (name "Net-(C6-Pad2)") (class "Default")
      (node (ref "C6") (pin "2") (pinfunction "2_2") (pintype "passive"))
      (node (ref "R3") (pin "2") (pinfunction "2_2") (pintype "passive"))
    )
    (net (code "19") (name "Net-(C9-Pad1)") (class "Default")
      (node (ref "C9") (pin "1") (pinfunction "1_1") (pintype "passive"))
      (node (ref "R4") (pin "1") (pinfunction "1_1") (pintype "passive"))
    )
    (net (code "20") (name "Net-(C18-Pad1)") (class "Default")
      (node (ref "C18") (pin "1") (pinfunction "1_1") (pintype "passive"))
      (node (ref "R8") (pin "1") (pinfunction "1_1") (pintype "passive"))
    )
    (net (code "21") (name "Net-(C20-Pad1)") (class "Default")
      (node (ref "C20") (pin "1") (pinfunction "1_1") (pintype "passive"))
      (node (ref "R6") (pin "1") (pinfunction "1_1") (pintype "passive"))
    )
    (net (code "22") (name "Net-(CN2-N)") (class "Default")
      (node (ref "C10") (pin "1") (pinfunction "1_1") (pintype "passive"))
      (node (ref "C12") (pin "1") (pinfunction "1_1") (pintype "passive"))
      (node (ref "C16") (pin "1") (pinfunction "1_1") (pintype "passive"))
      (node (ref "C6") (pin "1") (pinfunction "1_1") (pintype "passive"))
      (node (ref "CN2") (pin "2") (pinfunction "N_2") (pintype "passive"))
      (node (ref "L6") (pin "1") (pinfunction "1_1") (pintype "passive"))
    )
    (net (code "23") (name "Net-(CN2-P)") (class "Default")
      (node (ref "C19") (pin "2") (pinfunction "2_2") (pintype "passive"))
      (node (ref "C20") (pin "2") (pinfunction "2_2") (pintype "passive"))
      (node (ref "C24") (pin "2") (pinfunction "2_2") (pintype "passive"))
      (node (ref "C25") (pin "2") (pinfunction "2_2") (pintype "passive"))
      (node (ref "CN2") (pin "1") (pinfunction "P_1") (pintype "passive"))
      (node (ref "L1") (pin "2") (pinfunction "2_2") (pintype "passive"))
    )
    (net (code "24") (name "Net-(LED1-K)") (class "Default")
      (node (ref "LED1") (pin "2") (pinfunction "K_2") (pintype "passive"))
      (node (ref "R28") (pin "1") (pinfunction "1_1") (pintype "passive"))
    )
    (net (code "25") (name "Net-(LED2-K)") (class "Default")
      (node (ref "LED2") (pin "2") (pinfunction "K_2") (pintype "passive"))
      (node (ref "R29") (pin "1") (pinfunction "1_1") (pintype "passive"))
    )
    (net (code "26") (name "Net-(Q1-B)") (class "Default")
      (node (ref "Q1") (pin "1") (pinfunction "B_1") (pintype "passive"))
      (node (ref "R25") (pin "2") (pinfunction "2_2") (pintype "passive"))
      (node (ref "R26") (pin "2") (pinfunction "2_2") (pintype "passive"))
    )
    (net (code "27") (name "Net-(U1-AVDD)") (class "Default")
      (node (ref "C22") (pin "1") (pinfunction "1_1") (pintype "passive"))
      (node (ref "U1") (pin "14") (pinfunction "AVDD_14") (pintype "power_in"))
    )
    (net (code "28") (name "Net-(U1-BST_A)") (class "Default")
      (node (ref "C3") (pin "2") (pinfunction "2_2") (pintype "passive"))
      (node (ref "U1") (pin "44") (pinfunction "BST_A_44") (pintype "power_in"))
    )
    (net (code "29") (name "Net-(U1-BST_B)") (class "Default")
      (node (ref "C7") (pin "2") (pinfunction "2_2") (pintype "passive"))
      (node (ref "U1") (pin "43") (pinfunction "BST_B_43") (pintype "power_in"))
    )
    (net (code "30") (name "Net-(U1-BST_C)") (class "Default")
      (node (ref "C33") (pin "2") (pinfunction "2_2") (pintype "passive"))
      (node (ref "U1") (pin "24") (pinfunction "BST_C_24") (pintype "power_in"))
    )
    (net (code "31") (name "Net-(U1-BST_D)") (class "Default")
      (node (ref "C38") (pin "2") (pinfunction "2_2") (pintype "passive"))
      (node (ref "U1") (pin "23") (pinfunction "BST_D_23") (pintype "power_in"))
    )
    (net (code "32") (name "Net-(U1-C_START)") (class "Default")
      (node (ref "C50") (pin "1") (pinfunction "1_1") (pintype "passive"))
      (node (ref "U1") (pin "15") (pinfunction "C_START_15") (pintype "output"))
    )
    (net (code "33") (name "Net-(U1-DVDD)") (class "Default")
      (node (ref "C21") (pin "1") (pinfunction "1_1") (pintype "passive"))
      (node (ref "U1") (pin "11") (pinfunction "DVDD_11") (pintype "power_in"))
    )
    (net (code "34") (name "Net-(U1-FREQ_ADJ)") (class "Default")
      (node (ref "R24") (pin "2") (pinfunction "2_2") (pintype "passive"))
      (node (ref "U1") (pin "8") (pinfunction "FREQ_ADJ_8") (pintype "input"))
    )
    (net (code "35") (name "Net-(U1-GVDD_AB)") (class "Default")
      (node (ref "C30") (pin "1") (pinfunction "1_1") (pintype "passive"))
      (node (ref "R9") (pin "2") (pinfunction "2_2") (pintype "passive"))
      (node (ref "U1") (pin "1") (pinfunction "GVDD_AB_1") (pintype "power_in"))
    )
    (net (code "36") (name "Net-(U1-GVDD_CD)") (class "Default")
      (node (ref "C28") (pin "1") (pinfunction "1_1") (pintype "passive"))
      (node (ref "R11") (pin "2") (pinfunction "2_2") (pintype "passive"))
      (node (ref "U1") (pin "22") (pinfunction "GVDD_CD_22") (pintype "power_in"))
    )
    (net (code "37") (name "Net-(U1-OC_ADJ)") (class "Default")
      (node (ref "R18") (pin "2") (pinfunction "2_2") (pintype "passive"))
      (node (ref "U1") (pin "7") (pinfunction "OC_ADJ_7") (pintype "input"))
    )
    (net (code "38") (name "Net-(U1-OUT_B)") (class "Default")
      (node (ref "C38") (pin "1") (pinfunction "1_1") (pintype "passive"))
      (node (ref "C7") (pin "1") (pinfunction "1_1") (pintype "passive"))
      (node (ref "L1") (pin "1") (pinfunction "1_1") (pintype "passive"))
      (node (ref "U1") (pin "27") (pinfunction "OUT_D_27") (pintype "power_in"))
      (node (ref "U1") (pin "28") (pinfunction "OUT_D_28") (pintype "power_in"))
      (node (ref "U1") (pin "35") (pinfunction "OUT_B_35") (pintype "power_in"))
    )
    (net (code "39") (name "Net-(U1-OUT_C)") (class "Default")
      (node (ref "C3") (pin "1") (pinfunction "1_1") (pintype "passive"))
      (node (ref "C33") (pin "1") (pinfunction "1_1") (pintype "passive"))
      (node (ref "L6") (pin "2") (pinfunction "2_2") (pintype "passive"))
      (node (ref "U1") (pin "32") (pinfunction "OUT_C_32") (pintype "power_in"))
      (node (ref "U1") (pin "39") (pinfunction "OUT_A_39") (pintype "power_in"))
      (node (ref "U1") (pin "40") (pinfunction "OUT_A_40") (pintype "power_in"))
    )
    (net (code "40") (name "Net-(U1-VDD)") (class "Default")
      (node (ref "C29") (pin "1") (pinfunction "1_1") (pintype "passive"))
      (node (ref "L2") (pin "2") (pinfunction "2_2") (pintype "passive"))
      (node (ref "U1") (pin "2") (pinfunction "VDD_2") (pintype "power_in"))
    )
    (net (code "41") (name "Net-(U2A-IN1-)") (class "Default")
      (node (ref "C4") (pin "2") (pinfunction "2_2") (pintype "passive"))
      (node (ref "R1") (pin "1") (pinfunction "1_1") (pintype "passive"))
      (node (ref "R5") (pin "2") (pinfunction "2_2") (pintype "passive"))
      (node (ref "U2") (pin "2") (pinfunction "IN1-_2") (pintype "passive"))
    )
    (net (code "42") (name "Net-(U2A-Out1)") (class "Default")
      (node (ref "C18") (pin "2") (pinfunction "2_2") (pintype "passive"))
      (node (ref "C4") (pin "1") (pinfunction "1_1") (pintype "passive"))
      (node (ref "R1") (pin "2") (pinfunction "2_2") (pintype "passive"))
      (node (ref "R7") (pin "1") (pinfunction "1_1") (pintype "passive"))
      (node (ref "U2") (pin "1") (pinfunction "Out1_1") (pintype "passive"))
    )
    (net (code "43") (name "Net-(U2B-IN2-)") (class "Default")
      (node (ref "C5") (pin "2") (pinfunction "2_2") (pintype "passive"))
      (node (ref "R2") (pin "1") (pinfunction "1_1") (pintype "passive"))
      (node (ref "R7") (pin "2") (pinfunction "2_2") (pintype "passive"))
      (node (ref "U2") (pin "6") (pinfunction "IN2-_6") (pintype "passive"))
    )
    (net (code "44") (name "Net-(U2B-Out2)") (class "Default")
      (node (ref "C5") (pin "1") (pinfunction "1_1") (pintype "passive"))
      (node (ref "C9") (pin "2") (pinfunction "2_2") (pintype "passive"))
      (node (ref "R2") (pin "2") (pinfunction "2_2") (pintype "passive"))
      (node (ref "U2") (pin "7") (pinfunction "Out2_7") (pintype "passive"))
    )
    (net (code "45") (name "VBAT") (class "Default")
      (node (ref "C1") (pin "2") (pinfunction "2_2") (pintype "passive"))
      (node (ref "C11") (pin "1") (pinfunction "1_1") (pintype "passive"))
      (node (ref "C27") (pin "1") (pinfunction "1_1") (pintype "passive"))
      (node (ref "C35") (pin "1") (pinfunction "1_1") (pintype "passive"))
      (node (ref "C36") (pin "2") (pinfunction "2_2") (pintype "passive"))
      (node (ref "C37") (pin "1") (pinfunction "1_1") (pintype "passive"))
      (node (ref "CN3") (pin "1") (pinfunction "P_1") (pintype "passive"))
      (node (ref "U1") (pin "29") (pinfunction "PVDD_CD_29") (pintype "power_in"))
      (node (ref "U1") (pin "30") (pinfunction "PVDD_CD_30") (pintype "power_in"))
      (node (ref "U1") (pin "31") (pinfunction "PVDD_CD_31") (pintype "power_in"))
      (node (ref "U1") (pin "36") (pinfunction "PVDD_AB_36") (pintype "power_in"))
      (node (ref "U1") (pin "37") (pinfunction "PVDD_AB_37") (pintype "power_in"))
      (node (ref "U1") (pin "38") (pinfunction "PVDD_AB_38") (pintype "power_in"))
    )
    (net (code "46") (name "unconnected-(CN4-Pad3)") (class "Default")
      (node (ref "CN4") (pin "3") (pinfunction "3_3") (pintype "passive"))
    )
    (net (code "47") (name "unconnected-(DB1-Pad6)") (class "Default")
      (node (ref "DB1") (pin "6") (pinfunction "6_6") (pintype "passive"))
    )
    (net (code "48") (name "unconnected-(DB1-Pad7)") (class "Default")
      (node (ref "DB1") (pin "7") (pinfunction "7_7") (pintype "passive"))
    )
    (net (code "49") (name "unconnected-(U1-OC_IOM-Pad9)") (class "Default")
      (node (ref "U1") (pin "9") (pinfunction "OC_IOM_9") (pintype "bidirectional+no_connect"))
    )
    (net (code "50") (name "unconnected-(U1-OC_IOP-Pad10)") (class "Default")
      (node (ref "U1") (pin "10") (pinfunction "OC_IOP_10") (pintype "bidirectional+no_connect"))
    )
  )
)
